# vykObv.net
KiCad netlist of a schematic drawn in EAGLE
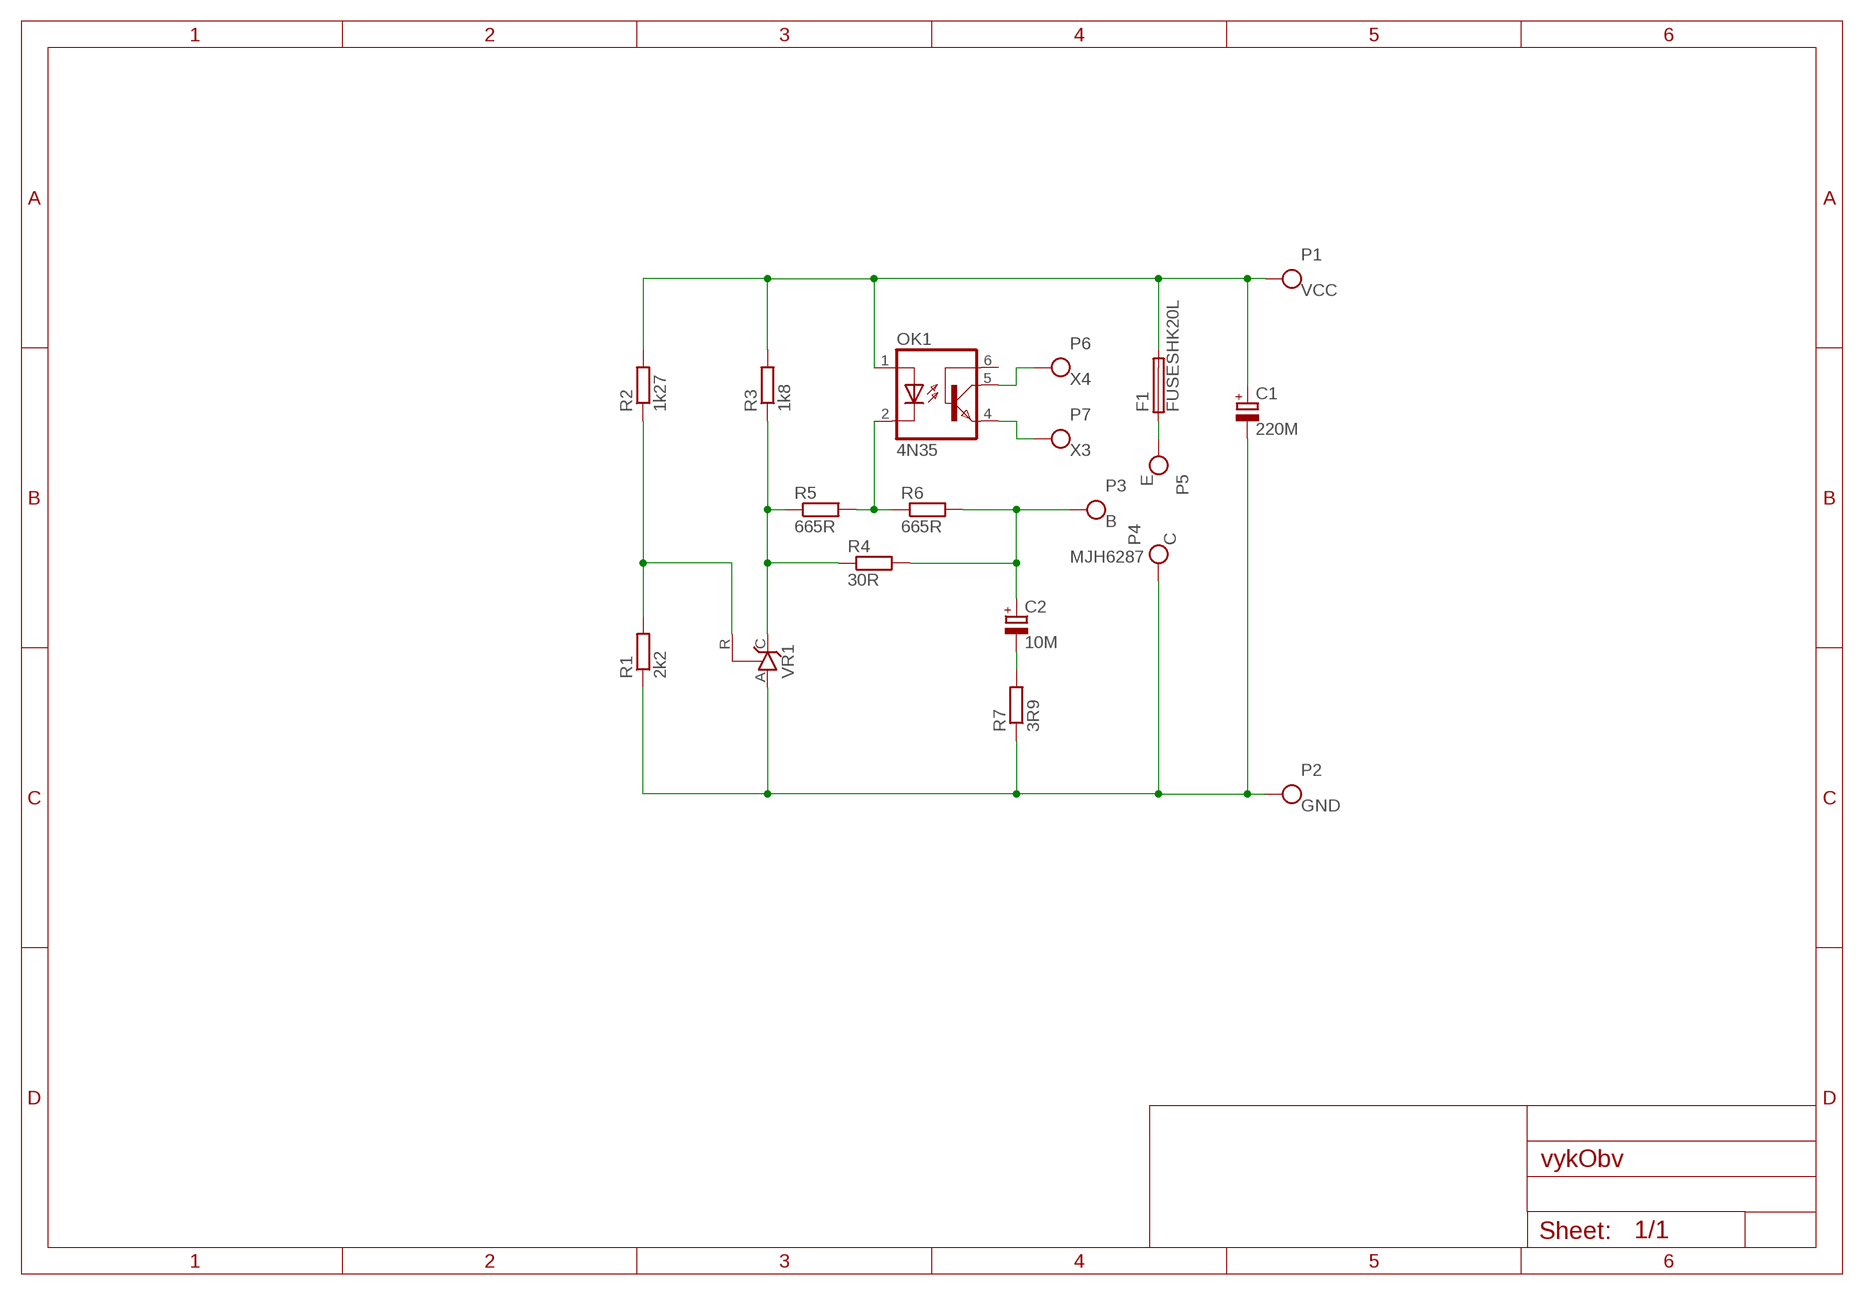
[diagram p0: schematic, sheet 1]

(export (version "E")
  (design (tool "Eeschema 10.0.6"))
  (components
    (comp (ref "C1")
      (value "220M")
      (footprint "eagle-import:E3,5-8")
      (libsource (lib "eagle-import") (part "CPOL-EUE3.5-8"))
    )
    (comp (ref "C2")
      (value "10M")
      (footprint "eagle-import:E22-6")
      (libsource (lib "eagle-import") (part "CPOL-EUE22-6AXIAL"))
    )
    (comp (ref "F1")
      (value "FUSESHK20L")
      (footprint "eagle-import:SHK20L")
      (libsource (lib "eagle-import") (part "FUSESHK20L"))
    )
    (comp (ref "OK1")
      (value "4N35")
      (footprint "eagle-import:DIL06")
      (fields (field (name "MF") "FAIRCHILD SEMICONDUCTOR"))
      (libsource (lib "eagle-import") (part "4N35"))
    )
    (comp (ref "P1")
      (value "VCC")
      (footprint "eagle-import:PAD2.5MM")
      (libsource (lib "eagle-import") (part "PADPAD2.5MM"))
    )
    (comp (ref "P2")
      (value "GND")
      (footprint "eagle-import:PAD2.5MM")
      (libsource (lib "eagle-import") (part "PADPAD2.5MM"))
    )
    (comp (ref "P3")
      (value "B")
      (footprint "eagle-import:PAD2.5MM")
      (libsource (lib "eagle-import") (part "PADPAD2.5MM"))
    )
    (comp (ref "P4")
      (value "C")
      (footprint "eagle-import:PAD2.5MM")
      (libsource (lib "eagle-import") (part "PADPAD2.5MM"))
    )
    (comp (ref "P5")
      (value "E")
      (footprint "eagle-import:PAD2.5MM")
      (libsource (lib "eagle-import") (part "PADPAD2.5MM"))
    )
    (comp (ref "P6")
      (value "X4")
      (footprint "eagle-import:PAD1.6MM")
      (libsource (lib "eagle-import") (part "PADPAD1.6MM"))
    )
    (comp (ref "P7")
      (value "X3")
      (footprint "eagle-import:PAD1.6MM")
      (libsource (lib "eagle-import") (part "PADPAD1.6MM"))
    )
    (comp (ref "R1")
      (value "2k2")
      (footprint "eagle-import:0207_10")
      (libsource (lib "eagle-import") (part "R-EU_0207/10"))
    )
    (comp (ref "R2")
      (value "1k27")
      (footprint "eagle-import:0207_10")
      (libsource (lib "eagle-import") (part "R-EU_0207/10"))
    )
    (comp (ref "R3")
      (value "1k8")
      (footprint "eagle-import:0207_10")
      (libsource (lib "eagle-import") (part "R-EU_0207/10"))
    )
    (comp (ref "R4")
      (value "30R")
      (footprint "eagle-import:0207_10")
      (libsource (lib "eagle-import") (part "R-EU_0207/10"))
    )
    (comp (ref "R5")
      (value "665R")
      (footprint "eagle-import:0207_10")
      (libsource (lib "eagle-import") (part "R-EU_0207/10"))
    )
    (comp (ref "R6")
      (value "665R")
      (footprint "eagle-import:0207_10")
      (libsource (lib "eagle-import") (part "R-EU_0207/10"))
    )
    (comp (ref "R7")
      (value "3R9")
      (footprint "eagle-import:0207_10")
      (libsource (lib "eagle-import") (part "R-EU_0207/10"))
    )
    (comp (ref "VR1")
      (value "TL431CLP")
      (footprint "eagle-import:TO92-CLP")
      (libsource (lib "eagle-import") (part "TL431CLP"))
    )
  )
  (nets
    (net (code "1") (name "Net-(C1-Pad-)") (class "Default")
      (node (ref "C1") (pin "-") (pinfunction "-_-") (pintype "passive"))
      (node (ref "P2") (pin "P$1") (pinfunction "P$1_P$1") (pintype "passive"))
      (node (ref "P4") (pin "P$1") (pinfunction "P$1_P$1") (pintype "passive"))
      (node (ref "R1") (pin "1") (pinfunction "1_1") (pintype "passive"))
      (node (ref "R7") (pin "1") (pinfunction "1_1") (pintype "passive"))
      (node (ref "VR1") (pin "A") (pinfunction "A_A") (pintype "passive"))
    )
    (net (code "2") (name "Net-(C2-Pad+)") (class "Default")
      (node (ref "C2") (pin "+") (pinfunction "+_+") (pintype "passive"))
      (node (ref "P3") (pin "P$1") (pinfunction "P$1_P$1") (pintype "passive"))
      (node (ref "R4") (pin "2") (pinfunction "2_2") (pintype "passive"))
      (node (ref "R6") (pin "2") (pinfunction "2_2") (pintype "passive"))
    )
    (net (code "3") (name "Net-(C2-Pad-)") (class "Default")
      (node (ref "C2") (pin "-") (pinfunction "-_-") (pintype "passive"))
      (node (ref "R7") (pin "2") (pinfunction "2_2") (pintype "passive"))
    )
    (net (code "4") (name "Net-(F1-1-Pad1A)") (class "Default")
      (node (ref "F1") (pin "1A") (pinfunction "1_1A") (pintype "passive"))
      (node (ref "F1") (pin "1B") (pinfunction "1_1B") (pintype "passive"))
      (node (ref "P5") (pin "P$1") (pinfunction "P$1_P$1") (pintype "passive"))
    )
    (net (code "5") (name "Net-(OK1-A)") (class "Default")
      (node (ref "C1") (pin "+") (pinfunction "+_+") (pintype "passive"))
      (node (ref "F1") (pin "2A") (pinfunction "2_2A") (pintype "passive"))
      (node (ref "F1") (pin "2B") (pinfunction "2_2B") (pintype "passive"))
      (node (ref "OK1") (pin "1") (pinfunction "A_1") (pintype "passive"))
      (node (ref "P1") (pin "P$1") (pinfunction "P$1_P$1") (pintype "passive"))
      (node (ref "R2") (pin "2") (pinfunction "2_2") (pintype "passive"))
      (node (ref "R3") (pin "2") (pinfunction "2_2") (pintype "passive"))
    )
    (net (code "6") (name "Net-(OK1-C)") (class "Default")
      (node (ref "OK1") (pin "2") (pinfunction "C_2") (pintype "passive"))
      (node (ref "R5") (pin "2") (pinfunction "2_2") (pintype "passive"))
      (node (ref "R6") (pin "1") (pinfunction "1_1") (pintype "passive"))
    )
    (net (code "7") (name "Net-(OK1-COL)") (class "Default")
      (node (ref "OK1") (pin "5") (pinfunction "COL_5") (pintype "passive"))
      (node (ref "P6") (pin "P$1") (pinfunction "P$1_P$1") (pintype "passive"))
    )
    (net (code "8") (name "Net-(OK1-EMI)") (class "Default")
      (node (ref "OK1") (pin "4") (pinfunction "EMI_4") (pintype "passive"))
      (node (ref "P7") (pin "P$1") (pinfunction "P$1_P$1") (pintype "passive"))
    )
    (net (code "9") (name "Net-(R1-Pad2)") (class "Default")
      (node (ref "R1") (pin "2") (pinfunction "2_2") (pintype "passive"))
      (node (ref "R2") (pin "1") (pinfunction "1_1") (pintype "passive"))
      (node (ref "VR1") (pin "R") (pinfunction "R_R") (pintype "passive"))
    )
    (net (code "10") (name "Net-(R3-Pad1)") (class "Default")
      (node (ref "R3") (pin "1") (pinfunction "1_1") (pintype "passive"))
      (node (ref "R4") (pin "1") (pinfunction "1_1") (pintype "passive"))
      (node (ref "R5") (pin "1") (pinfunction "1_1") (pintype "passive"))
      (node (ref "VR1") (pin "C") (pinfunction "C_C") (pintype "passive"))
    )
    (net (code "11") (name "unconnected-(OK1-BAS-Pad6)") (class "Default")
      (node (ref "OK1") (pin "6") (pinfunction "BAS_6") (pintype "passive"))
    )
  )
)
